# M206.net
KiCad netlist of a schematic drawn in EAGLE
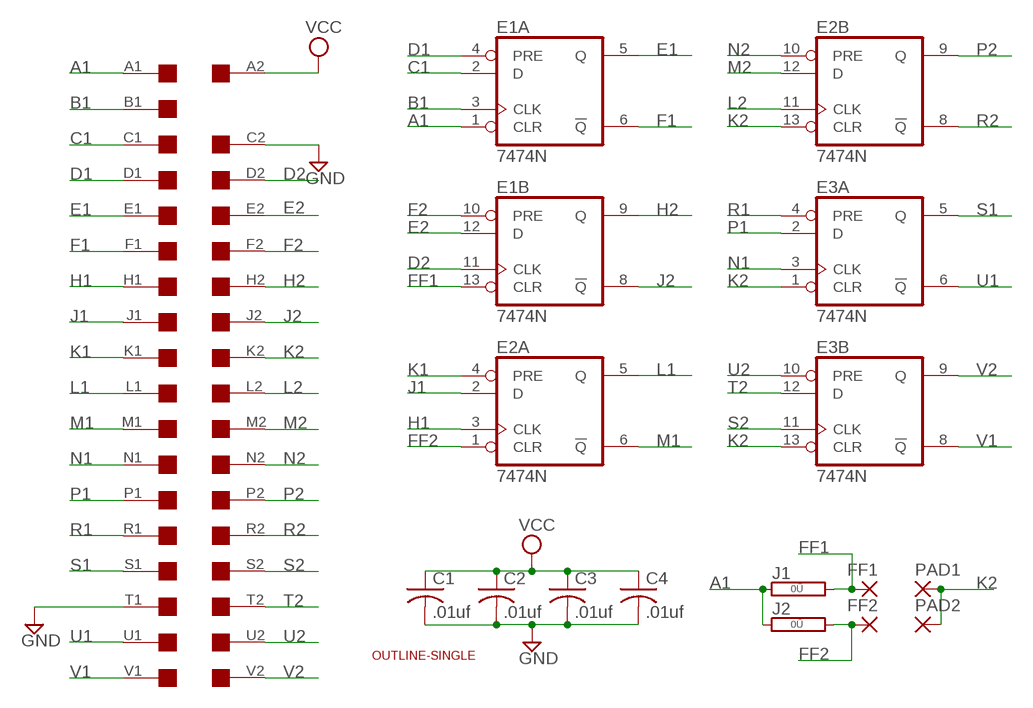
[diagram p0: schematic, sheet 1]

(export (version "E")
  (design (tool "Eeschema 10.0.6"))
  (components
    (comp (ref "C1")
      (value ".01uf")
      (footprint "eagle-import:C050-025X075")
      (libsource (lib "eagle-import") (part "C-US050-025X075"))
    )
    (comp (ref "C2")
      (value ".01uf")
      (footprint "eagle-import:C050-025X075")
      (libsource (lib "eagle-import") (part "C-US050-025X075"))
    )
    (comp (ref "C3")
      (value ".01uf")
      (footprint "eagle-import:C050-025X075")
      (libsource (lib "eagle-import") (part "C-US050-025X075"))
    )
    (comp (ref "C4")
      (value ".01uf")
      (footprint "eagle-import:C050-025X075")
      (libsource (lib "eagle-import") (part "C-US050-025X075"))
    )
    (comp (ref "E1")
      (value "7474N")
      (footprint "eagle-import:DIL14")
      (libsource (lib "eagle-import") (part "7474NS"))
    )
    (comp (ref "E2")
      (value "7474N")
      (footprint "eagle-import:DIL14")
      (libsource (lib "eagle-import") (part "7474NS"))
    )
    (comp (ref "E3")
      (value "7474N")
      (footprint "eagle-import:DIL14")
      (libsource (lib "eagle-import") (part "7474NS"))
    )
    (comp (ref "FF1")
      (value "1,6/0,8")
      (footprint "eagle-import:1,6_0,8")
      (libsource (lib "eagle-import") (part "1,6/0,8"))
    )
    (comp (ref "FF2")
      (value "1,6/0,8")
      (footprint "eagle-import:1,6_0,8")
      (libsource (lib "eagle-import") (part "1,6/0,8"))
    )
    (comp (ref "J1")
      (value "0R")
      (footprint "eagle-import:0R_10")
      (libsource (lib "eagle-import") (part "0R"))
    )
    (comp (ref "J2")
      (value "0R")
      (footprint "eagle-import:0R_10")
      (libsource (lib "eagle-import") (part "0R"))
    )
    (comp (ref "PAD1")
      (value "1,6/0,8")
      (footprint "eagle-import:1,6_0,8")
      (libsource (lib "eagle-import") (part "1,6/0,8"))
    )
    (comp (ref "PAD2")
      (value "1,6/0,8")
      (footprint "eagle-import:1,6_0,8")
      (libsource (lib "eagle-import") (part "1,6/0,8"))
    )
    (comp (ref "U$1")
      (value "OUTLINE-SINGLE")
      (footprint "eagle-import:SINGLE")
      (libsource (lib "eagle-import") (part "OUTLINE-SINGLE"))
    )
    (comp (ref "U$4")
      (value "SINGLE")
      (footprint "eagle-import:EDGE-CON2")
      (libsource (lib "eagle-import") (part "SINGLE"))
    )
  )
  (nets
    (net (code "1") (name "/A1") (class "Default")
      (node (ref "E1") (pin "1") (pinfunction "CLR_1") (pintype "input"))
      (node (ref "J1") (pin "1") (pinfunction "1_1") (pintype "passive"))
      (node (ref "J2") (pin "1") (pinfunction "1_1") (pintype "passive"))
      (node (ref "U$4") (pin "A1") (pinfunction "1_A1") (pintype "bidirectional"))
    )
    (net (code "2") (name "/B1") (class "Default")
      (node (ref "E1") (pin "3") (pinfunction "CLK_3") (pintype "input"))
      (node (ref "U$4") (pin "B1") (pinfunction "1_B1") (pintype "bidirectional"))
    )
    (net (code "3") (name "/C1") (class "Default")
      (node (ref "E1") (pin "2") (pinfunction "D_2") (pintype "input"))
      (node (ref "U$4") (pin "C1") (pinfunction "1_C1") (pintype "bidirectional"))
    )
    (net (code "4") (name "/D1") (class "Default")
      (node (ref "E1") (pin "4") (pinfunction "PRE_4") (pintype "input"))
      (node (ref "U$4") (pin "D1") (pinfunction "1_D1") (pintype "bidirectional"))
    )
    (net (code "5") (name "/D2") (class "Default")
      (node (ref "E1") (pin "11") (pinfunction "CLK_11") (pintype "input"))
      (node (ref "U$4") (pin "D2") (pinfunction "1_D2") (pintype "bidirectional"))
    )
    (net (code "6") (name "/E1") (class "Default")
      (node (ref "E1") (pin "5") (pinfunction "Q_5") (pintype "output"))
      (node (ref "U$4") (pin "E1") (pinfunction "1_E1") (pintype "bidirectional"))
    )
    (net (code "7") (name "/E2") (class "Default")
      (node (ref "E1") (pin "12") (pinfunction "D_12") (pintype "input"))
      (node (ref "U$4") (pin "E2") (pinfunction "1_E2") (pintype "bidirectional"))
    )
    (net (code "8") (name "/F1") (class "Default")
      (node (ref "E1") (pin "6") (pinfunction "~{Q}_6") (pintype "output"))
      (node (ref "U$4") (pin "F1") (pinfunction "1_F1") (pintype "bidirectional"))
    )
    (net (code "9") (name "/F2") (class "Default")
      (node (ref "E1") (pin "10") (pinfunction "PRE_10") (pintype "input"))
      (node (ref "U$4") (pin "F2") (pinfunction "1_F2") (pintype "bidirectional"))
    )
    (net (code "10") (name "/FF1") (class "Default")
      (node (ref "E1") (pin "13") (pinfunction "CLR_13") (pintype "input"))
      (node (ref "FF1") (pin "1") (pinfunction "P_1") (pintype "passive"))
      (node (ref "J1") (pin "2") (pinfunction "2_2") (pintype "passive"))
    )
    (net (code "11") (name "/FF2") (class "Default")
      (node (ref "E2") (pin "1") (pinfunction "CLR_1") (pintype "input"))
      (node (ref "FF2") (pin "1") (pinfunction "P_1") (pintype "passive"))
      (node (ref "J2") (pin "2") (pinfunction "2_2") (pintype "passive"))
    )
    (net (code "12") (name "/H1") (class "Default")
      (node (ref "E2") (pin "3") (pinfunction "CLK_3") (pintype "input"))
      (node (ref "U$4") (pin "H1") (pinfunction "1_H1") (pintype "bidirectional"))
    )
    (net (code "13") (name "/H2") (class "Default")
      (node (ref "E1") (pin "9") (pinfunction "Q_9") (pintype "output"))
      (node (ref "U$4") (pin "H2") (pinfunction "1_H2") (pintype "bidirectional"))
    )
    (net (code "14") (name "/J1") (class "Default")
      (node (ref "E2") (pin "2") (pinfunction "D_2") (pintype "input"))
      (node (ref "U$4") (pin "J1") (pinfunction "1_J1") (pintype "bidirectional"))
    )
    (net (code "15") (name "/J2") (class "Default")
      (node (ref "E1") (pin "8") (pinfunction "~{Q}_8") (pintype "output"))
      (node (ref "U$4") (pin "J2") (pinfunction "1_J2") (pintype "bidirectional"))
    )
    (net (code "16") (name "/K1") (class "Default")
      (node (ref "E2") (pin "4") (pinfunction "PRE_4") (pintype "input"))
      (node (ref "U$4") (pin "K1") (pinfunction "1_K1") (pintype "bidirectional"))
    )
    (net (code "17") (name "/K2") (class "Default")
      (node (ref "E2") (pin "13") (pinfunction "CLR_13") (pintype "input"))
      (node (ref "E3") (pin "1") (pinfunction "CLR_1") (pintype "input"))
      (node (ref "E3") (pin "13") (pinfunction "CLR_13") (pintype "input"))
      (node (ref "PAD1") (pin "1") (pinfunction "P_1") (pintype "passive"))
      (node (ref "PAD2") (pin "1") (pinfunction "P_1") (pintype "passive"))
      (node (ref "U$4") (pin "K2") (pinfunction "1_K2") (pintype "bidirectional"))
    )
    (net (code "18") (name "/L1") (class "Default")
      (node (ref "E2") (pin "5") (pinfunction "Q_5") (pintype "output"))
      (node (ref "U$4") (pin "L1") (pinfunction "1_L1") (pintype "bidirectional"))
    )
    (net (code "19") (name "/L2") (class "Default")
      (node (ref "E2") (pin "11") (pinfunction "CLK_11") (pintype "input"))
      (node (ref "U$4") (pin "L2") (pinfunction "1_L2") (pintype "bidirectional"))
    )
    (net (code "20") (name "/M1") (class "Default")
      (node (ref "E2") (pin "6") (pinfunction "~{Q}_6") (pintype "output"))
      (node (ref "U$4") (pin "M1") (pinfunction "1_M1") (pintype "bidirectional"))
    )
    (net (code "21") (name "/M2") (class "Default")
      (node (ref "E2") (pin "12") (pinfunction "D_12") (pintype "input"))
      (node (ref "U$4") (pin "M2") (pinfunction "1_M2") (pintype "bidirectional"))
    )
    (net (code "22") (name "/N1") (class "Default")
      (node (ref "E3") (pin "3") (pinfunction "CLK_3") (pintype "input"))
      (node (ref "U$4") (pin "N1") (pinfunction "1_N1") (pintype "bidirectional"))
    )
    (net (code "23") (name "/N2") (class "Default")
      (node (ref "E2") (pin "10") (pinfunction "PRE_10") (pintype "input"))
      (node (ref "U$4") (pin "N2") (pinfunction "1_N2") (pintype "bidirectional"))
    )
    (net (code "24") (name "/P1") (class "Default")
      (node (ref "E3") (pin "2") (pinfunction "D_2") (pintype "input"))
      (node (ref "U$4") (pin "P1") (pinfunction "1_P1") (pintype "bidirectional"))
    )
    (net (code "25") (name "/P2") (class "Default")
      (node (ref "E2") (pin "9") (pinfunction "Q_9") (pintype "output"))
      (node (ref "U$4") (pin "P2") (pinfunction "1_P2") (pintype "bidirectional"))
    )
    (net (code "26") (name "/R1") (class "Default")
      (node (ref "E3") (pin "4") (pinfunction "PRE_4") (pintype "input"))
      (node (ref "U$4") (pin "R1") (pinfunction "1_R1") (pintype "bidirectional"))
    )
    (net (code "27") (name "/R2") (class "Default")
      (node (ref "E2") (pin "8") (pinfunction "~{Q}_8") (pintype "output"))
      (node (ref "U$4") (pin "R2") (pinfunction "1_R2") (pintype "bidirectional"))
    )
    (net (code "28") (name "/S1") (class "Default")
      (node (ref "E3") (pin "5") (pinfunction "Q_5") (pintype "output"))
      (node (ref "U$4") (pin "S1") (pinfunction "1_S1") (pintype "bidirectional"))
    )
    (net (code "29") (name "/S2") (class "Default")
      (node (ref "E3") (pin "11") (pinfunction "CLK_11") (pintype "input"))
      (node (ref "U$4") (pin "S2") (pinfunction "1_S2") (pintype "bidirectional"))
    )
    (net (code "30") (name "/T2") (class "Default")
      (node (ref "E3") (pin "12") (pinfunction "D_12") (pintype "input"))
      (node (ref "U$4") (pin "T2") (pinfunction "1_T2") (pintype "bidirectional"))
    )
    (net (code "31") (name "/U1") (class "Default")
      (node (ref "E3") (pin "6") (pinfunction "~{Q}_6") (pintype "output"))
      (node (ref "U$4") (pin "U1") (pinfunction "1_U1") (pintype "bidirectional"))
    )
    (net (code "32") (name "/U2") (class "Default")
      (node (ref "E3") (pin "10") (pinfunction "PRE_10") (pintype "input"))
      (node (ref "U$4") (pin "U2") (pinfunction "1_U2") (pintype "bidirectional"))
    )
    (net (code "33") (name "/V1") (class "Default")
      (node (ref "E3") (pin "8") (pinfunction "~{Q}_8") (pintype "output"))
      (node (ref "U$4") (pin "V1") (pinfunction "1_V1") (pintype "bidirectional"))
    )
    (net (code "34") (name "/V2") (class "Default")
      (node (ref "E3") (pin "9") (pinfunction "Q_9") (pintype "output"))
      (node (ref "U$4") (pin "V2") (pinfunction "1_V2") (pintype "bidirectional"))
    )
    (net (code "35") (name "GND") (class "Default")
      (node (ref "C1") (pin "2") (pinfunction "2_2") (pintype "passive"))
      (node (ref "C2") (pin "2") (pinfunction "2_2") (pintype "passive"))
      (node (ref "C3") (pin "2") (pinfunction "2_2") (pintype "passive"))
      (node (ref "C4") (pin "2") (pinfunction "2_2") (pintype "passive"))
      (node (ref "U$4") (pin "C2") (pinfunction "1_C2") (pintype "bidirectional"))
      (node (ref "U$4") (pin "T1") (pinfunction "1_T1") (pintype "bidirectional"))
    )
    (net (code "36") (name "VCC") (class "Default")
      (node (ref "C1") (pin "1") (pinfunction "1_1") (pintype "passive"))
      (node (ref "C2") (pin "1") (pinfunction "1_1") (pintype "passive"))
      (node (ref "C3") (pin "1") (pinfunction "1_1") (pintype "passive"))
      (node (ref "C4") (pin "1") (pinfunction "1_1") (pintype "passive"))
      (node (ref "U$4") (pin "A2") (pinfunction "1_A2") (pintype "bidirectional"))
    )
  )
)
